# Sheet3.net
KiCad netlist of a schematic drawn in Altium Designer
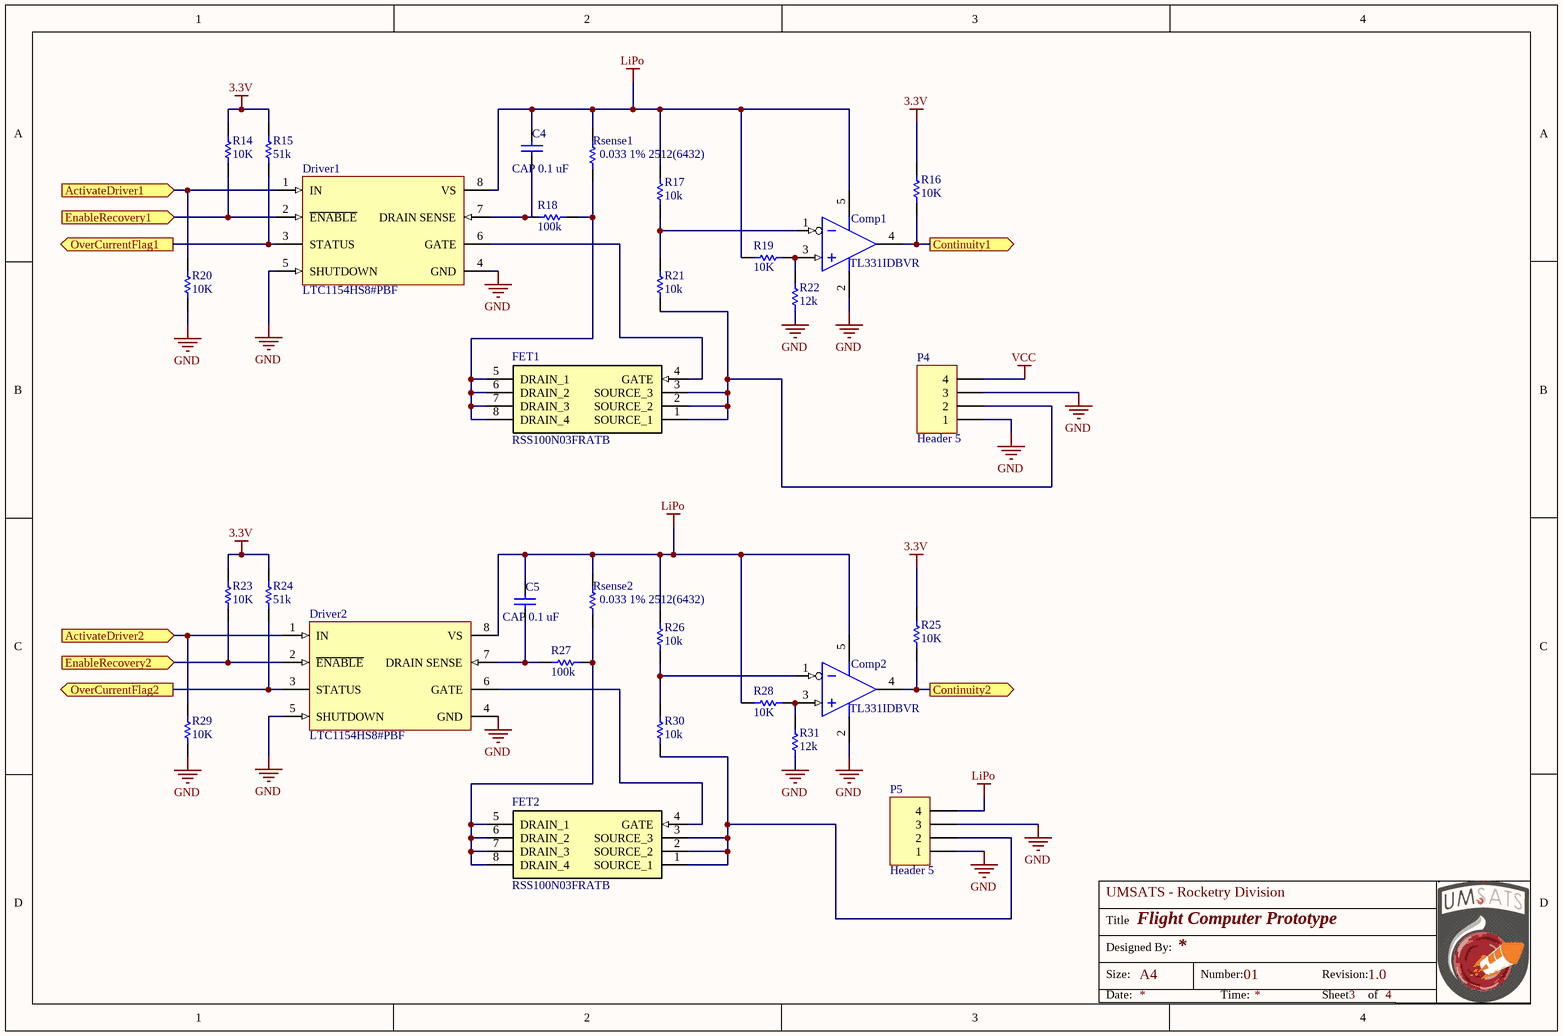
[diagram p0: Sheet3.SchDoc]

(export (version "E")
  (design (tool "Eeschema 10.0.6"))
  (components
    (comp (ref "C4")
      (value "CAP 0.1 uF")
      (footprint "06035C104KAT4A")
      (description "Capacitor")
      (fields (field (name "PUBLISHER") "Altium Limited"))
      (libsource (lib "Miscellaneous Devices") (part "Cap"))
    )
    (comp (ref "C5")
      (value "CAP 0.1 uF")
      (footprint "06035C104KAT4A")
      (description "Capacitor")
      (fields (field (name "PUBLISHER") "Altium Limited"))
      (libsource (lib "Miscellaneous Devices") (part "Cap"))
    )
    (comp (ref "Comp1")
      (value "TL331IDBVR")
      (footprint "DBV0005A_M")
      (fields (field (name "MANUFACTURER") "TexasInstruments"))
      (libsource (lib "Altium Content Vault") (part "TI-TL331-EP-DBV5"))
    )
    (comp (ref "Comp2")
      (value "TL331IDBVR")
      (footprint "DBV0005A_M")
      (fields (field (name "MANUFACTURER") "TexasInstruments"))
      (libsource (lib "Altium Content Vault") (part "TI-TL331-EP-DBV5"))
    )
    (comp (ref "Driver1")
      (value "LTC1154HS8#PBF")
      (footprint "LT-S8-8_N")
      (description "High-Side Micropower MOSFET Driver, 22 V Vin MAX, 8-pin SOIC (S8-8), -40 to 150 degC, Pb-Free")
      (fields (field (name "MANUFACTURER") "Linear Technology"))
      (libsource (lib "Altium Content Vault") (part "LT-LTC1154-X8-8"))
    )
    (comp (ref "Driver2")
      (value "LTC1154HS8#PBF")
      (footprint "LT-S8-8_N")
      (description "High-Side Micropower MOSFET Driver, 22 V Vin MAX, 8-pin SOIC (S8-8), -40 to 150 degC, Pb-Free")
      (fields (field (name "MANUFACTURER") "Linear Technology"))
      (libsource (lib "Altium Content Vault") (part "LT-LTC1154-X8-8"))
    )
    (comp (ref "FET1")
      (value "RSS100N03FRATB")
      (footprint "SamacSys:SOIC127P600X165-8N")
      (description "MOSFET (N-Channel)")
      (fields (field (name "MOUSER PART NUMBER") "755-RSS100N03FRATB"))
      (libsource (lib "SamacSys") (part "RSS100N03FRATB"))
    )
    (comp (ref "FET2")
      (value "RSS100N03FRATB")
      (footprint "SamacSys:SOIC127P600X165-8N")
      (description "MOSFET (N-Channel)")
      (fields (field (name "MOUSER PART NUMBER") "755-RSS100N03FRATB"))
      (libsource (lib "SamacSys") (part "RSS100N03FRATB"))
    )
    (comp (ref "P4")
      (value "Header 5")
      (footprint "BarrierBlock6.35mm:BarrierBlock")
      (description "Header, 4-Pin")
      (fields (field (name "PUBLISHER") "Altium Limited"))
      (libsource (lib "Miscellaneous Connectors") (part "Header 4"))
    )
    (comp (ref "P5")
      (value "Header 5")
      (footprint "BarrierBlock6.35mm:BarrierBlock")
      (description "Header, 4-Pin")
      (fields (field (name "PUBLISHER") "Altium Limited"))
      (libsource (lib "Miscellaneous Connectors") (part "Header 4"))
    )
    (comp (ref "R14")
      (value "10K")
      (footprint "RK73H1JTTD1002F")
      (description "Resistor")
      (fields (field (name "PUBLISHER") "Altium Limited"))
      (libsource (lib "Miscellaneous Devices") (part "Res1"))
    )
    (comp (ref "R15")
      (value "51k")
      (footprint "RK73H1JTTD1002F")
      (description "Resistor")
      (fields (field (name "PUBLISHER") "Altium Limited"))
      (libsource (lib "Miscellaneous Devices") (part "Res1"))
    )
    (comp (ref "R16")
      (value "10K")
      (footprint "RK73H1JTTD1002F")
      (description "Resistor")
      (fields (field (name "PUBLISHER") "Altium Limited"))
      (libsource (lib "Miscellaneous Devices") (part "Res1"))
    )
    (comp (ref "R17")
      (value "10k")
      (footprint "RK73H1JTTD1002F")
      (description "Resistor")
      (fields (field (name "PUBLISHER") "Altium Limited"))
      (libsource (lib "Miscellaneous Devices") (part "Res1"))
    )
    (comp (ref "R18")
      (value "100k")
      (footprint "RK73H1JTTD1002F")
      (description "Resistor")
      (fields (field (name "PUBLISHER") "Altium Limited"))
      (libsource (lib "Miscellaneous Devices") (part "Res1"))
    )
    (comp (ref "R19")
      (value "10K")
      (footprint "RK73H1JTTD1002F")
      (description "Resistor")
      (fields (field (name "PUBLISHER") "Altium Limited"))
      (libsource (lib "Miscellaneous Devices") (part "Res1"))
    )
    (comp (ref "R20")
      (value "10K")
      (footprint "RK73H1JTTD1002F")
      (description "Resistor")
      (fields (field (name "PUBLISHER") "Altium Limited"))
      (libsource (lib "Miscellaneous Devices") (part "Res1"))
    )
    (comp (ref "R21")
      (value "10k")
      (footprint "RK73H1JTTD1002F")
      (description "Resistor")
      (fields (field (name "PUBLISHER") "Altium Limited"))
      (libsource (lib "Miscellaneous Devices") (part "Res1"))
    )
    (comp (ref "R22")
      (value "12k")
      (footprint "RK73H1JTTD1002F")
      (description "Resistor")
      (fields (field (name "PUBLISHER") "Altium Limited"))
      (libsource (lib "Miscellaneous Devices") (part "Res1"))
    )
    (comp (ref "R23")
      (value "10K")
      (footprint "RK73H1JTTD1002F")
      (description "Resistor")
      (fields (field (name "PUBLISHER") "Altium Limited"))
      (libsource (lib "Miscellaneous Devices") (part "Res1"))
    )
    (comp (ref "R24")
      (value "51k")
      (footprint "RK73H1JTTD1002F")
      (description "Resistor")
      (fields (field (name "PUBLISHER") "Altium Limited"))
      (libsource (lib "Miscellaneous Devices") (part "Res1"))
    )
    (comp (ref "R25")
      (value "10K")
      (footprint "RK73H1JTTD1002F")
      (description "Resistor")
      (fields (field (name "PUBLISHER") "Altium Limited"))
      (libsource (lib "Miscellaneous Devices") (part "Res1"))
    )
    (comp (ref "R26")
      (value "10k")
      (footprint "RK73H1JTTD1002F")
      (description "Resistor")
      (fields (field (name "PUBLISHER") "Altium Limited"))
      (libsource (lib "Miscellaneous Devices") (part "Res1"))
    )
    (comp (ref "R27")
      (value "100k")
      (footprint "RK73H1JTTD1002F")
      (description "Resistor")
      (fields (field (name "PUBLISHER") "Altium Limited"))
      (libsource (lib "Miscellaneous Devices") (part "Res1"))
    )
    (comp (ref "R28")
      (value "10K")
      (footprint "RK73H1JTTD1002F")
      (description "Resistor")
      (fields (field (name "PUBLISHER") "Altium Limited"))
      (libsource (lib "Miscellaneous Devices") (part "Res1"))
    )
    (comp (ref "R29")
      (value "10K")
      (footprint "RK73H1JTTD1002F")
      (description "Resistor")
      (fields (field (name "PUBLISHER") "Altium Limited"))
      (libsource (lib "Miscellaneous Devices") (part "Res1"))
    )
    (comp (ref "R30")
      (value "10k")
      (footprint "RK73H1JTTD1002F")
      (description "Resistor")
      (fields (field (name "PUBLISHER") "Altium Limited"))
      (libsource (lib "Miscellaneous Devices") (part "Res1"))
    )
    (comp (ref "R31")
      (value "12k")
      (footprint "RK73H1JTTD1002F")
      (description "Resistor")
      (fields (field (name "PUBLISHER") "Altium Limited"))
      (libsource (lib "Miscellaneous Devices") (part "Res1"))
    )
    (comp (ref "Rsense1")
      (value "0.033 1% 2512(6432)")
      (footprint "RESC2512(6432)_N")
      (description "8M66 1W 1% 2512 (6432 Metric)  SMD")
      (fields (field (name "POWER") "1 W") (field (name "TOLERANCE") "1 %"))
      (libsource (lib "Altium Content Vault") (part "RES"))
    )
    (comp (ref "Rsense2")
      (value "0.033 1% 2512(6432)")
      (footprint "RESC2512(6432)_N")
      (description "8M66 1W 1% 2512 (6432 Metric)  SMD")
      (fields (field (name "POWER") "1 W") (field (name "TOLERANCE") "1 %"))
      (libsource (lib "Altium Content Vault") (part "RES"))
    )
  )
  (nets
    (net (code "1") (name "/ActivateDriver1") (class "Default")
      (node (ref "Driver1") (pin "1") (pinfunction "IN_1") (pintype "input"))
      (node (ref "R20") (pin "2") (pinfunction "2_2") (pintype "passive"))
    )
    (net (code "2") (name "/ActivateDriver2") (class "Default")
      (node (ref "Driver2") (pin "1") (pinfunction "IN_1") (pintype "input"))
      (node (ref "R29") (pin "2") (pinfunction "2_2") (pintype "passive"))
    )
    (net (code "3") (name "/Continuity1") (class "Default")
      (node (ref "Comp1") (pin "4") (pinfunction "OUT_4") (pintype "tri_state"))
      (node (ref "R16") (pin "1") (pinfunction "1_1") (pintype "passive"))
    )
    (net (code "4") (name "/Continuity2") (class "Default")
      (node (ref "Comp2") (pin "4") (pinfunction "OUT_4") (pintype "tri_state"))
      (node (ref "R25") (pin "1") (pinfunction "1_1") (pintype "passive"))
    )
    (net (code "5") (name "/EnableRecovery1") (class "Default")
      (node (ref "Driver1") (pin "2") (pinfunction "~{ENABLE}_2") (pintype "input"))
      (node (ref "R14") (pin "1") (pinfunction "1_1") (pintype "passive"))
    )
    (net (code "6") (name "/EnableRecovery2") (class "Default")
      (node (ref "Driver2") (pin "2") (pinfunction "~{ENABLE}_2") (pintype "input"))
      (node (ref "R23") (pin "1") (pinfunction "1_1") (pintype "passive"))
    )
    (net (code "7") (name "/OverCurrentFlag1") (class "Default")
      (node (ref "Driver1") (pin "3") (pinfunction "STATUS_3") (pintype "open_collector"))
      (node (ref "R15") (pin "1") (pinfunction "1_1") (pintype "passive"))
    )
    (net (code "8") (name "/OverCurrentFlag2") (class "Default")
      (node (ref "Driver2") (pin "3") (pinfunction "STATUS_3") (pintype "open_collector"))
      (node (ref "R24") (pin "1") (pinfunction "1_1") (pintype "passive"))
    )
    (net (code "9") (name "3.3V") (class "Default")
      (node (ref "R14") (pin "2") (pinfunction "2_2") (pintype "passive"))
      (node (ref "R15") (pin "2") (pinfunction "2_2") (pintype "passive"))
      (node (ref "R16") (pin "2") (pinfunction "2_2") (pintype "passive"))
      (node (ref "R23") (pin "2") (pinfunction "2_2") (pintype "passive"))
      (node (ref "R24") (pin "2") (pinfunction "2_2") (pintype "passive"))
      (node (ref "R25") (pin "2") (pinfunction "2_2") (pintype "passive"))
    )
    (net (code "10") (name "GND") (class "Default")
      (node (ref "Comp1") (pin "2") (pinfunction "VCC-/GND_2") (pintype "power_in"))
      (node (ref "Comp2") (pin "2") (pinfunction "VCC-/GND_2") (pintype "power_in"))
      (node (ref "Driver1") (pin "4") (pinfunction "GND_4") (pintype "power_in"))
      (node (ref "Driver1") (pin "5") (pinfunction "SHUTDOWN_5") (pintype "input"))
      (node (ref "Driver2") (pin "4") (pinfunction "GND_4") (pintype "power_in"))
      (node (ref "Driver2") (pin "5") (pinfunction "SHUTDOWN_5") (pintype "input"))
      (node (ref "P4") (pin "1") (pinfunction "1_1") (pintype "passive"))
      (node (ref "P4") (pin "3") (pinfunction "3_3") (pintype "passive"))
      (node (ref "P5") (pin "1") (pinfunction "1_1") (pintype "passive"))
      (node (ref "P5") (pin "3") (pinfunction "3_3") (pintype "passive"))
      (node (ref "R20") (pin "1") (pinfunction "1_1") (pintype "passive"))
      (node (ref "R22") (pin "1") (pinfunction "1_1") (pintype "passive"))
      (node (ref "R29") (pin "1") (pinfunction "1_1") (pintype "passive"))
      (node (ref "R31") (pin "1") (pinfunction "1_1") (pintype "passive"))
    )
    (net (code "11") (name "LiPo") (class "Default")
      (node (ref "C4") (pin "1") (pinfunction "1_1") (pintype "passive"))
      (node (ref "C5") (pin "1") (pinfunction "1_1") (pintype "passive"))
      (node (ref "Comp1") (pin "5") (pinfunction "VCC_5") (pintype "power_in"))
      (node (ref "Comp2") (pin "5") (pinfunction "VCC_5") (pintype "power_in"))
      (node (ref "Driver1") (pin "8") (pinfunction "VS_8") (pintype "power_in"))
      (node (ref "Driver2") (pin "8") (pinfunction "VS_8") (pintype "power_in"))
      (node (ref "P5") (pin "4") (pinfunction "4_4") (pintype "passive"))
      (node (ref "R17") (pin "2") (pinfunction "2_2") (pintype "passive"))
      (node (ref "R19") (pin "2") (pinfunction "2_2") (pintype "passive"))
      (node (ref "R26") (pin "2") (pinfunction "2_2") (pintype "passive"))
      (node (ref "R28") (pin "2") (pinfunction "2_2") (pintype "passive"))
      (node (ref "Rsense1") (pin "2") (pinfunction "2_2") (pintype "passive"))
      (node (ref "Rsense2") (pin "2") (pinfunction "2_2") (pintype "passive"))
    )
    (net (code "12") (name "Net-(Comp1-IN+)") (class "Default")
      (node (ref "Comp1") (pin "3") (pinfunction "IN+_3") (pintype "input"))
      (node (ref "R19") (pin "1") (pinfunction "1_1") (pintype "passive"))
      (node (ref "R22") (pin "2") (pinfunction "2_2") (pintype "passive"))
    )
    (net (code "13") (name "Net-(Comp1-IN-)") (class "Default")
      (node (ref "Comp1") (pin "1") (pinfunction "IN-_1") (pintype "input"))
      (node (ref "R17") (pin "1") (pinfunction "1_1") (pintype "passive"))
      (node (ref "R21") (pin "2") (pinfunction "2_2") (pintype "passive"))
    )
    (net (code "14") (name "Net-(Comp2-IN+)") (class "Default")
      (node (ref "Comp2") (pin "3") (pinfunction "IN+_3") (pintype "input"))
      (node (ref "R28") (pin "1") (pinfunction "1_1") (pintype "passive"))
      (node (ref "R31") (pin "2") (pinfunction "2_2") (pintype "passive"))
    )
    (net (code "15") (name "Net-(Comp2-IN-)") (class "Default")
      (node (ref "Comp2") (pin "1") (pinfunction "IN-_1") (pintype "input"))
      (node (ref "R26") (pin "1") (pinfunction "1_1") (pintype "passive"))
      (node (ref "R30") (pin "2") (pinfunction "2_2") (pintype "passive"))
    )
    (net (code "16") (name "Net-(Driver1-DRAIN_SENSE)") (class "Default")
      (node (ref "C4") (pin "2") (pinfunction "2_2") (pintype "passive"))
      (node (ref "Driver1") (pin "7") (pinfunction "DRAIN_SENSE_7") (pintype "input"))
      (node (ref "R18") (pin "2") (pinfunction "2_2") (pintype "passive"))
    )
    (net (code "17") (name "Net-(Driver1-GATE)") (class "Default")
      (node (ref "Driver1") (pin "6") (pinfunction "GATE_6") (pintype "tri_state"))
      (node (ref "FET1") (pin "4") (pinfunction "GATE_4") (pintype "input"))
    )
    (net (code "18") (name "Net-(Driver2-DRAIN_SENSE)") (class "Default")
      (node (ref "C5") (pin "2") (pinfunction "2_2") (pintype "passive"))
      (node (ref "Driver2") (pin "7") (pinfunction "DRAIN_SENSE_7") (pintype "input"))
      (node (ref "R27") (pin "2") (pinfunction "2_2") (pintype "passive"))
    )
    (net (code "19") (name "Net-(Driver2-GATE)") (class "Default")
      (node (ref "Driver2") (pin "6") (pinfunction "GATE_6") (pintype "tri_state"))
      (node (ref "FET2") (pin "4") (pinfunction "GATE_4") (pintype "input"))
    )
    (net (code "20") (name "Net-(FET1-DRAIN_1)") (class "Default")
      (node (ref "FET1") (pin "5") (pinfunction "DRAIN_1_5") (pintype "power_in"))
      (node (ref "FET1") (pin "6") (pinfunction "DRAIN_2_6") (pintype "power_in"))
      (node (ref "FET1") (pin "7") (pinfunction "DRAIN_3_7") (pintype "power_in"))
      (node (ref "FET1") (pin "8") (pinfunction "DRAIN_4_8") (pintype "power_in"))
      (node (ref "R18") (pin "1") (pinfunction "1_1") (pintype "passive"))
      (node (ref "Rsense1") (pin "1") (pinfunction "1_1") (pintype "passive"))
    )
    (net (code "21") (name "Net-(FET1-SOURCE_1)") (class "Default")
      (node (ref "FET1") (pin "1") (pinfunction "SOURCE_1_1") (pintype "power_in"))
      (node (ref "FET1") (pin "2") (pinfunction "SOURCE_2_2") (pintype "power_in"))
      (node (ref "FET1") (pin "3") (pinfunction "SOURCE_3_3") (pintype "power_in"))
      (node (ref "P4") (pin "2") (pinfunction "2_2") (pintype "passive"))
      (node (ref "R21") (pin "1") (pinfunction "1_1") (pintype "passive"))
    )
    (net (code "22") (name "Net-(FET2-DRAIN_1)") (class "Default")
      (node (ref "FET2") (pin "5") (pinfunction "DRAIN_1_5") (pintype "power_in"))
      (node (ref "FET2") (pin "6") (pinfunction "DRAIN_2_6") (pintype "power_in"))
      (node (ref "FET2") (pin "7") (pinfunction "DRAIN_3_7") (pintype "power_in"))
      (node (ref "FET2") (pin "8") (pinfunction "DRAIN_4_8") (pintype "power_in"))
      (node (ref "R27") (pin "1") (pinfunction "1_1") (pintype "passive"))
      (node (ref "Rsense2") (pin "1") (pinfunction "1_1") (pintype "passive"))
    )
    (net (code "23") (name "Net-(FET2-SOURCE_1)") (class "Default")
      (node (ref "FET2") (pin "1") (pinfunction "SOURCE_1_1") (pintype "power_in"))
      (node (ref "FET2") (pin "2") (pinfunction "SOURCE_2_2") (pintype "power_in"))
      (node (ref "FET2") (pin "3") (pinfunction "SOURCE_3_3") (pintype "power_in"))
      (node (ref "P5") (pin "2") (pinfunction "2_2") (pintype "passive"))
      (node (ref "R30") (pin "1") (pinfunction "1_1") (pintype "passive"))
    )
    (net (code "24") (name "VCC") (class "Default")
      (node (ref "P4") (pin "4") (pinfunction "4_4") (pintype "passive"))
    )
  )
)
